# Simple_VGA.net
KiCad netlist of a schematic drawn in EAGLE
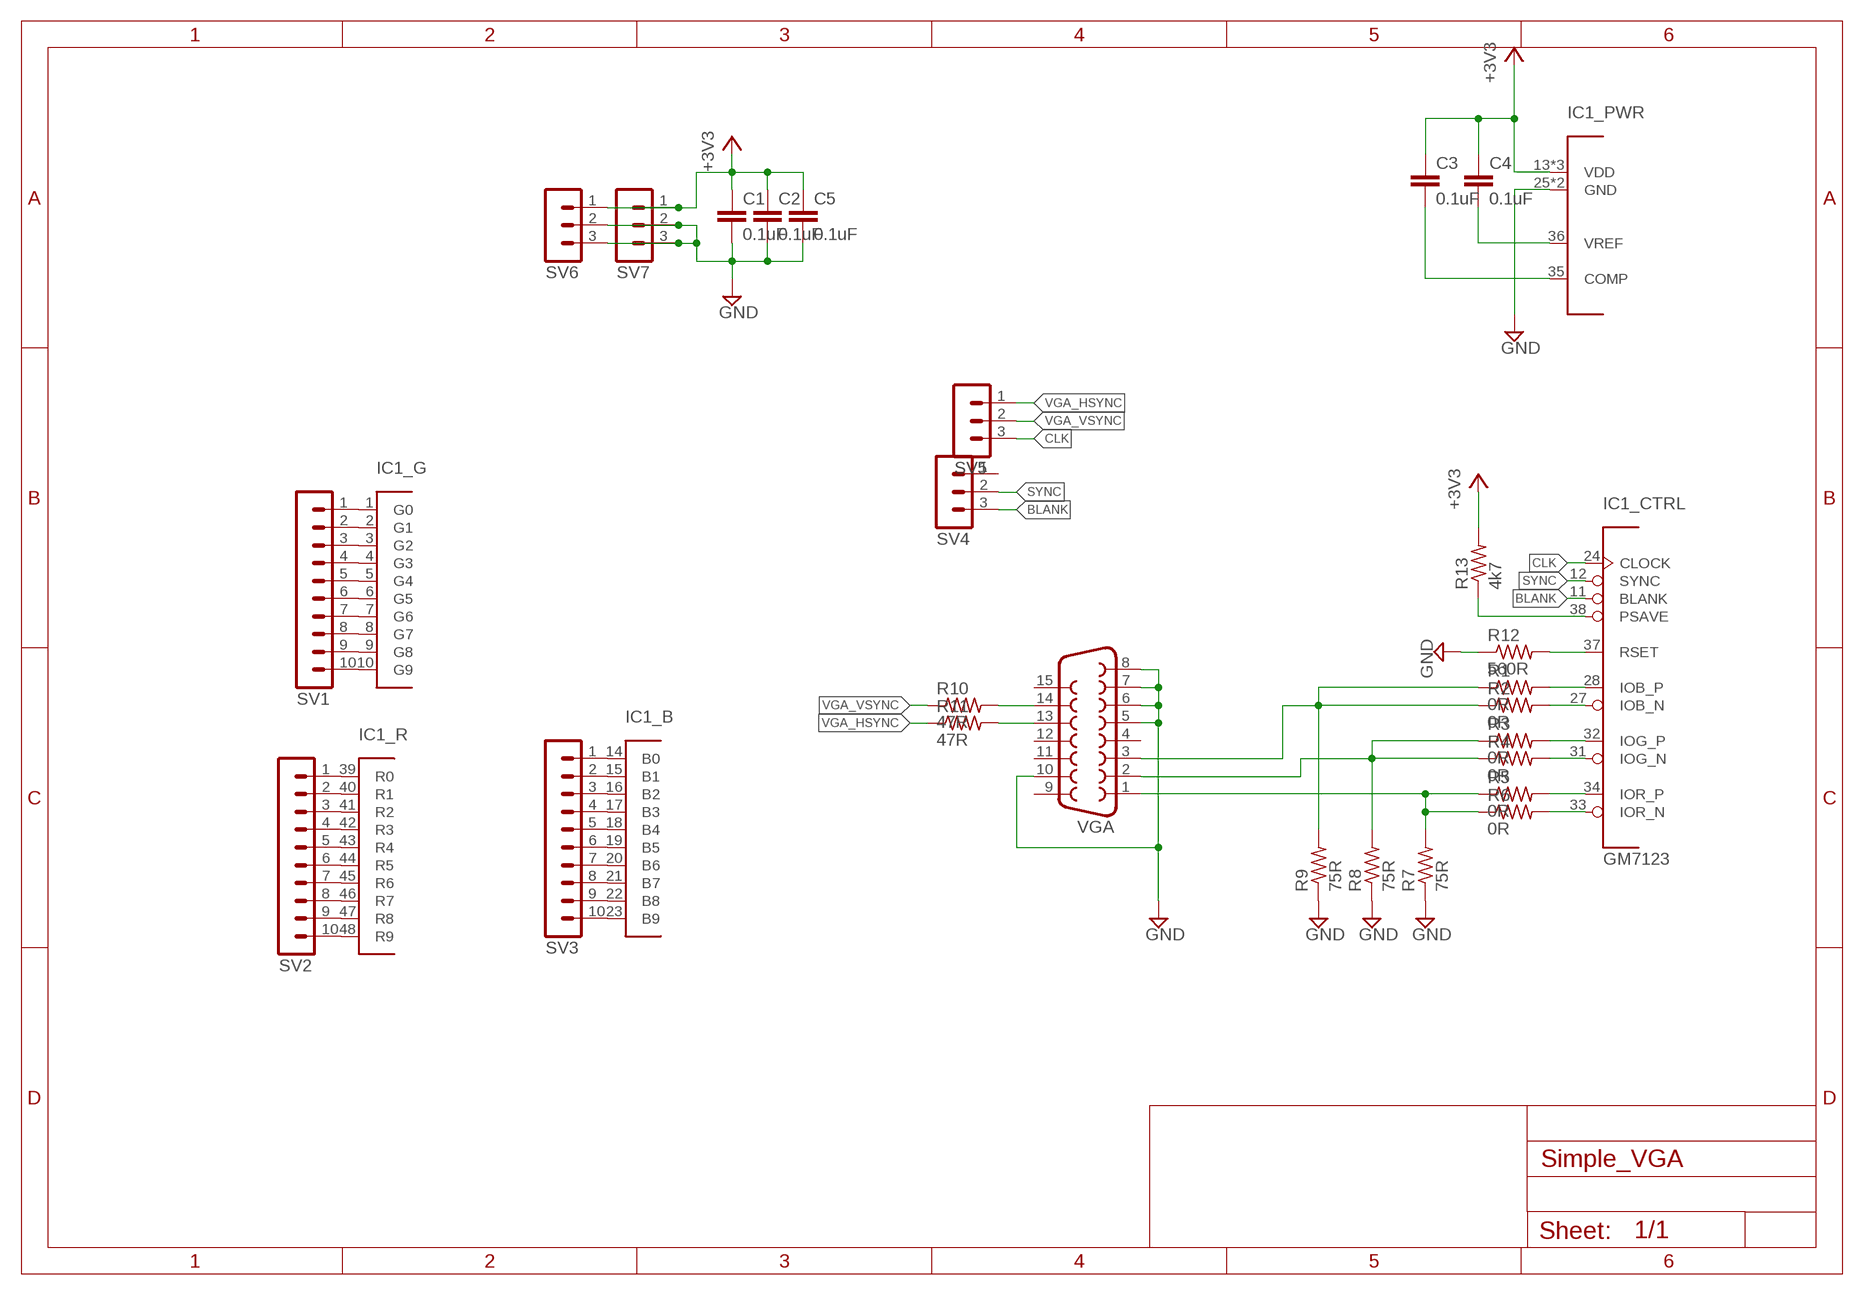
[diagram p0: schematic, sheet 1]

(export (version "E")
  (design (tool "Eeschema 10.0.6"))
  (components
    (comp (ref "C1")
      (value "0.1uF")
      (footprint "eagle-import:C1206")
      (libsource (lib "eagle-import") (part "C-EUC1206"))
    )
    (comp (ref "C2")
      (value "0.1uF")
      (footprint "eagle-import:C1206")
      (libsource (lib "eagle-import") (part "C-EUC1206"))
    )
    (comp (ref "C3")
      (value "0.1uF")
      (footprint "eagle-import:C1206")
      (libsource (lib "eagle-import") (part "C-EUC1206"))
    )
    (comp (ref "C4")
      (value "0.1uF")
      (footprint "eagle-import:C1206")
      (libsource (lib "eagle-import") (part "C-EUC1206"))
    )
    (comp (ref "C5")
      (value "0.1uF")
      (footprint "eagle-import:C1206")
      (libsource (lib "eagle-import") (part "C-EUC1206"))
    )
    (comp (ref "IC1")
      (value "GM7123")
      (footprint "eagle-import:TQFP48")
      (libsource (lib "eagle-import") (part "GM7123"))
    )
    (comp (ref "R1")
      (value "0R")
      (footprint "eagle-import:R1206")
      (libsource (lib "eagle-import") (part "R-US_R1206"))
    )
    (comp (ref "R2")
      (value "0R")
      (footprint "eagle-import:R1206")
      (libsource (lib "eagle-import") (part "R-US_R1206"))
    )
    (comp (ref "R3")
      (value "0R")
      (footprint "eagle-import:R1206")
      (libsource (lib "eagle-import") (part "R-US_R1206"))
    )
    (comp (ref "R4")
      (value "0R")
      (footprint "eagle-import:R1206")
      (libsource (lib "eagle-import") (part "R-US_R1206"))
    )
    (comp (ref "R5")
      (value "0R")
      (footprint "eagle-import:R1206")
      (libsource (lib "eagle-import") (part "R-US_R1206"))
    )
    (comp (ref "R6")
      (value "0R")
      (footprint "eagle-import:R1206")
      (libsource (lib "eagle-import") (part "R-US_R1206"))
    )
    (comp (ref "R7")
      (value "75R")
      (footprint "eagle-import:R1206")
      (libsource (lib "eagle-import") (part "R-US_R1206"))
    )
    (comp (ref "R8")
      (value "75R")
      (footprint "eagle-import:R1206")
      (libsource (lib "eagle-import") (part "R-US_R1206"))
    )
    (comp (ref "R9")
      (value "75R")
      (footprint "eagle-import:R1206")
      (libsource (lib "eagle-import") (part "R-US_R1206"))
    )
    (comp (ref "R10")
      (value "47R")
      (footprint "eagle-import:R1206")
      (libsource (lib "eagle-import") (part "R-US_R1206"))
    )
    (comp (ref "R11")
      (value "47R")
      (footprint "eagle-import:R1206")
      (libsource (lib "eagle-import") (part "R-US_R1206"))
    )
    (comp (ref "R12")
      (value "560R")
      (footprint "eagle-import:R1206")
      (libsource (lib "eagle-import") (part "R-US_R1206"))
    )
    (comp (ref "R13")
      (value "4k7")
      (footprint "eagle-import:R1206")
      (libsource (lib "eagle-import") (part "R-US_R1206"))
    )
    (comp (ref "SV1")
      (value "MA10-1")
      (footprint "eagle-import:MA10-1")
      (libsource (lib "eagle-import") (part "MA10-1"))
    )
    (comp (ref "SV2")
      (value "MA10-1")
      (footprint "eagle-import:MA10-1")
      (fields (field (name "OC_FARNELL") "unknown") (field (name "OC_NEWARK") "unknown"))
      (libsource (lib "eagle-import") (part "MA10-1"))
    )
    (comp (ref "SV3")
      (value "MA10-1")
      (footprint "eagle-import:MA10-1")
      (fields (field (name "OC_FARNELL") "unknown") (field (name "OC_NEWARK") "unknown"))
      (libsource (lib "eagle-import") (part "MA10-1"))
    )
    (comp (ref "SV4")
      (value "MA03-1")
      (footprint "eagle-import:MA03-1")
      (fields (field (name "OC_FARNELL") "unknown") (field (name "OC_NEWARK") "unknown"))
      (libsource (lib "eagle-import") (part "MA03-1"))
    )
    (comp (ref "SV5")
      (value "MA03-1")
      (footprint "eagle-import:MA03-1")
      (libsource (lib "eagle-import") (part "MA03-1"))
    )
    (comp (ref "SV6")
      (value "MA03-1")
      (footprint "eagle-import:MA03-1")
      (fields (field (name "OC_FARNELL") "unknown") (field (name "OC_NEWARK") "unknown"))
      (libsource (lib "eagle-import") (part "MA03-1"))
    )
    (comp (ref "SV7")
      (value "MA03-1")
      (footprint "eagle-import:MA03-1")
      (fields (field (name "OC_FARNELL") "unknown") (field (name "OC_NEWARK") "unknown"))
      (libsource (lib "eagle-import") (part "MA03-1"))
    )
    (comp (ref "VGA")
      (value "F15HDH")
      (footprint "eagle-import:HDF15H")
      (libsource (lib "eagle-import") (part "F15HDH"))
    )
  )
  (nets
    (net (code "1") (name "+3V3") (class "Default")
      (node (ref "C1") (pin "1") (pinfunction "1_1") (pintype "passive"))
      (node (ref "C2") (pin "1") (pinfunction "1_1") (pintype "passive"))
      (node (ref "C3") (pin "1") (pinfunction "1_1") (pintype "passive"))
      (node (ref "C4") (pin "1") (pinfunction "1_1") (pintype "passive"))
      (node (ref "C5") (pin "1") (pinfunction "1_1") (pintype "passive"))
      (node (ref "IC1") (pin "13") (pinfunction "VDD_13") (pintype "power_in"))
      (node (ref "IC1") (pin "29") (pinfunction "VDD_29") (pintype "power_in"))
      (node (ref "IC1") (pin "30") (pinfunction "VDD_30") (pintype "power_in"))
      (node (ref "R13") (pin "2") (pinfunction "2_2") (pintype "passive"))
      (node (ref "SV6") (pin "1") (pinfunction "1_1") (pintype "passive"))
      (node (ref "SV7") (pin "1") (pinfunction "1_1") (pintype "passive"))
    )
    (net (code "2") (name "BLANK") (class "Default")
      (node (ref "IC1") (pin "11") (pinfunction "BLANK_11") (pintype "input"))
      (node (ref "SV4") (pin "3") (pinfunction "3_3") (pintype "passive"))
    )
    (net (code "3") (name "CLK") (class "Default")
      (node (ref "IC1") (pin "24") (pinfunction "CLOCK_24") (pintype "input"))
      (node (ref "SV5") (pin "3") (pinfunction "3_3") (pintype "passive"))
    )
    (net (code "4") (name "GND") (class "Default")
      (node (ref "C1") (pin "2") (pinfunction "2_2") (pintype "passive"))
      (node (ref "C2") (pin "2") (pinfunction "2_2") (pintype "passive"))
      (node (ref "C5") (pin "2") (pinfunction "2_2") (pintype "passive"))
      (node (ref "IC1") (pin "25") (pinfunction "GND_25") (pintype "power_in"))
      (node (ref "IC1") (pin "26") (pinfunction "GND_26") (pintype "power_in"))
      (node (ref "R12") (pin "1") (pinfunction "1_1") (pintype "passive"))
      (node (ref "R7") (pin "1") (pinfunction "1_1") (pintype "passive"))
      (node (ref "R8") (pin "1") (pinfunction "1_1") (pintype "passive"))
      (node (ref "R9") (pin "1") (pinfunction "1_1") (pintype "passive"))
      (node (ref "SV6") (pin "2") (pinfunction "2_2") (pintype "passive"))
      (node (ref "SV6") (pin "3") (pinfunction "3_3") (pintype "passive"))
      (node (ref "SV7") (pin "2") (pinfunction "2_2") (pintype "passive"))
      (node (ref "SV7") (pin "3") (pinfunction "3_3") (pintype "passive"))
      (node (ref "VGA") (pin "10") (pinfunction "10_10") (pintype "passive"))
      (node (ref "VGA") (pin "5") (pinfunction "5_5") (pintype "passive"))
      (node (ref "VGA") (pin "6") (pinfunction "6_6") (pintype "passive"))
      (node (ref "VGA") (pin "7") (pinfunction "7_7") (pintype "passive"))
      (node (ref "VGA") (pin "8") (pinfunction "8_8") (pintype "passive"))
    )
    (net (code "5") (name "Net-(IC1A-B0)") (class "Default")
      (node (ref "IC1") (pin "14") (pinfunction "B0_14") (pintype "input"))
      (node (ref "SV3") (pin "1") (pinfunction "1_1") (pintype "passive"))
    )
    (net (code "6") (name "Net-(IC1A-B1)") (class "Default")
      (node (ref "IC1") (pin "15") (pinfunction "B1_15") (pintype "input"))
      (node (ref "SV3") (pin "2") (pinfunction "2_2") (pintype "passive"))
    )
    (net (code "7") (name "Net-(IC1A-B2)") (class "Default")
      (node (ref "IC1") (pin "16") (pinfunction "B2_16") (pintype "input"))
      (node (ref "SV3") (pin "3") (pinfunction "3_3") (pintype "passive"))
    )
    (net (code "8") (name "Net-(IC1A-B3)") (class "Default")
      (node (ref "IC1") (pin "17") (pinfunction "B3_17") (pintype "input"))
      (node (ref "SV3") (pin "4") (pinfunction "4_4") (pintype "passive"))
    )
    (net (code "9") (name "Net-(IC1A-B4)") (class "Default")
      (node (ref "IC1") (pin "18") (pinfunction "B4_18") (pintype "input"))
      (node (ref "SV3") (pin "5") (pinfunction "5_5") (pintype "passive"))
    )
    (net (code "10") (name "Net-(IC1A-B5)") (class "Default")
      (node (ref "IC1") (pin "19") (pinfunction "B5_19") (pintype "input"))
      (node (ref "SV3") (pin "6") (pinfunction "6_6") (pintype "passive"))
    )
    (net (code "11") (name "Net-(IC1A-B6)") (class "Default")
      (node (ref "IC1") (pin "20") (pinfunction "B6_20") (pintype "input"))
      (node (ref "SV3") (pin "7") (pinfunction "7_7") (pintype "passive"))
    )
    (net (code "12") (name "Net-(IC1A-B7)") (class "Default")
      (node (ref "IC1") (pin "21") (pinfunction "B7_21") (pintype "input"))
      (node (ref "SV3") (pin "8") (pinfunction "8_8") (pintype "passive"))
    )
    (net (code "13") (name "Net-(IC1A-B8)") (class "Default")
      (node (ref "IC1") (pin "22") (pinfunction "B8_22") (pintype "input"))
      (node (ref "SV3") (pin "9") (pinfunction "9_9") (pintype "passive"))
    )
    (net (code "14") (name "Net-(IC1A-B9)") (class "Default")
      (node (ref "IC1") (pin "23") (pinfunction "B9_23") (pintype "input"))
      (node (ref "SV3") (pin "10") (pinfunction "10_10") (pintype "passive"))
    )
    (net (code "15") (name "Net-(IC1B-IOB_N)") (class "Default")
      (node (ref "IC1") (pin "27") (pinfunction "IOB_N_27") (pintype "output"))
      (node (ref "R2") (pin "2") (pinfunction "2_2") (pintype "passive"))
    )
    (net (code "16") (name "Net-(IC1B-IOB_P)") (class "Default")
      (node (ref "IC1") (pin "28") (pinfunction "IOB_P_28") (pintype "output"))
      (node (ref "R1") (pin "2") (pinfunction "2_2") (pintype "passive"))
    )
    (net (code "17") (name "Net-(IC1B-IOG_N)") (class "Default")
      (node (ref "IC1") (pin "31") (pinfunction "IOG_N_31") (pintype "output"))
      (node (ref "R4") (pin "2") (pinfunction "2_2") (pintype "passive"))
    )
    (net (code "18") (name "Net-(IC1B-IOG_P)") (class "Default")
      (node (ref "IC1") (pin "32") (pinfunction "IOG_P_32") (pintype "output"))
      (node (ref "R3") (pin "2") (pinfunction "2_2") (pintype "passive"))
    )
    (net (code "19") (name "Net-(IC1B-IOR_N)") (class "Default")
      (node (ref "IC1") (pin "33") (pinfunction "IOR_N_33") (pintype "output"))
      (node (ref "R6") (pin "2") (pinfunction "2_2") (pintype "passive"))
    )
    (net (code "20") (name "Net-(IC1B-IOR_P)") (class "Default")
      (node (ref "IC1") (pin "34") (pinfunction "IOR_P_34") (pintype "output"))
      (node (ref "R5") (pin "2") (pinfunction "2_2") (pintype "passive"))
    )
    (net (code "21") (name "Net-(IC1B-PSAVE)") (class "Default")
      (node (ref "IC1") (pin "38") (pinfunction "PSAVE_38") (pintype "input"))
      (node (ref "R13") (pin "1") (pinfunction "1_1") (pintype "passive"))
    )
    (net (code "22") (name "Net-(IC1B-RSET)") (class "Default")
      (node (ref "IC1") (pin "37") (pinfunction "RSET_37") (pintype "input"))
      (node (ref "R12") (pin "2") (pinfunction "2_2") (pintype "passive"))
    )
    (net (code "23") (name "Net-(IC1C-G0)") (class "Default")
      (node (ref "IC1") (pin "1") (pinfunction "G0_1") (pintype "input"))
      (node (ref "SV1") (pin "1") (pinfunction "1_1") (pintype "passive"))
    )
    (net (code "24") (name "Net-(IC1C-G1)") (class "Default")
      (node (ref "IC1") (pin "2") (pinfunction "G1_2") (pintype "input"))
      (node (ref "SV1") (pin "2") (pinfunction "2_2") (pintype "passive"))
    )
    (net (code "25") (name "Net-(IC1C-G2)") (class "Default")
      (node (ref "IC1") (pin "3") (pinfunction "G2_3") (pintype "input"))
      (node (ref "SV1") (pin "3") (pinfunction "3_3") (pintype "passive"))
    )
    (net (code "26") (name "Net-(IC1C-G3)") (class "Default")
      (node (ref "IC1") (pin "4") (pinfunction "G3_4") (pintype "input"))
      (node (ref "SV1") (pin "4") (pinfunction "4_4") (pintype "passive"))
    )
    (net (code "27") (name "Net-(IC1C-G4)") (class "Default")
      (node (ref "IC1") (pin "5") (pinfunction "G4_5") (pintype "input"))
      (node (ref "SV1") (pin "5") (pinfunction "5_5") (pintype "passive"))
    )
    (net (code "28") (name "Net-(IC1C-G5)") (class "Default")
      (node (ref "IC1") (pin "6") (pinfunction "G5_6") (pintype "input"))
      (node (ref "SV1") (pin "6") (pinfunction "6_6") (pintype "passive"))
    )
    (net (code "29") (name "Net-(IC1C-G6)") (class "Default")
      (node (ref "IC1") (pin "7") (pinfunction "G6_7") (pintype "input"))
      (node (ref "SV1") (pin "7") (pinfunction "7_7") (pintype "passive"))
    )
    (net (code "30") (name "Net-(IC1C-G7)") (class "Default")
      (node (ref "IC1") (pin "8") (pinfunction "G7_8") (pintype "input"))
      (node (ref "SV1") (pin "8") (pinfunction "8_8") (pintype "passive"))
    )
    (net (code "31") (name "Net-(IC1C-G8)") (class "Default")
      (node (ref "IC1") (pin "9") (pinfunction "G8_9") (pintype "input"))
      (node (ref "SV1") (pin "9") (pinfunction "9_9") (pintype "passive"))
    )
    (net (code "32") (name "Net-(IC1C-G9)") (class "Default")
      (node (ref "IC1") (pin "10") (pinfunction "G9_10") (pintype "input"))
      (node (ref "SV1") (pin "10") (pinfunction "10_10") (pintype "passive"))
    )
    (net (code "33") (name "Net-(IC1D-COMP)") (class "Default")
      (node (ref "C3") (pin "2") (pinfunction "2_2") (pintype "passive"))
      (node (ref "IC1") (pin "35") (pinfunction "COMP_35") (pintype "power_in"))
    )
    (net (code "34") (name "Net-(IC1D-VREF)") (class "Default")
      (node (ref "C4") (pin "2") (pinfunction "2_2") (pintype "passive"))
      (node (ref "IC1") (pin "36") (pinfunction "VREF_36") (pintype "power_in"))
    )
    (net (code "35") (name "Net-(IC1E-R0)") (class "Default")
      (node (ref "IC1") (pin "39") (pinfunction "R0_39") (pintype "input"))
      (node (ref "SV2") (pin "1") (pinfunction "1_1") (pintype "passive"))
    )
    (net (code "36") (name "Net-(IC1E-R1)") (class "Default")
      (node (ref "IC1") (pin "40") (pinfunction "R1_40") (pintype "input"))
      (node (ref "SV2") (pin "2") (pinfunction "2_2") (pintype "passive"))
    )
    (net (code "37") (name "Net-(IC1E-R2)") (class "Default")
      (node (ref "IC1") (pin "41") (pinfunction "R2_41") (pintype "input"))
      (node (ref "SV2") (pin "3") (pinfunction "3_3") (pintype "passive"))
    )
    (net (code "38") (name "Net-(IC1E-R3)") (class "Default")
      (node (ref "IC1") (pin "42") (pinfunction "R3_42") (pintype "input"))
      (node (ref "SV2") (pin "4") (pinfunction "4_4") (pintype "passive"))
    )
    (net (code "39") (name "Net-(IC1E-R4)") (class "Default")
      (node (ref "IC1") (pin "43") (pinfunction "R4_43") (pintype "input"))
      (node (ref "SV2") (pin "5") (pinfunction "5_5") (pintype "passive"))
    )
    (net (code "40") (name "Net-(IC1E-R5)") (class "Default")
      (node (ref "IC1") (pin "44") (pinfunction "R5_44") (pintype "input"))
      (node (ref "SV2") (pin "6") (pinfunction "6_6") (pintype "passive"))
    )
    (net (code "41") (name "Net-(IC1E-R6)") (class "Default")
      (node (ref "IC1") (pin "45") (pinfunction "R6_45") (pintype "input"))
      (node (ref "SV2") (pin "7") (pinfunction "7_7") (pintype "passive"))
    )
    (net (code "42") (name "Net-(IC1E-R7)") (class "Default")
      (node (ref "IC1") (pin "46") (pinfunction "R7_46") (pintype "input"))
      (node (ref "SV2") (pin "8") (pinfunction "8_8") (pintype "passive"))
    )
    (net (code "43") (name "Net-(IC1E-R8)") (class "Default")
      (node (ref "IC1") (pin "47") (pinfunction "R8_47") (pintype "input"))
      (node (ref "SV2") (pin "9") (pinfunction "9_9") (pintype "passive"))
    )
    (net (code "44") (name "Net-(IC1E-R9)") (class "Default")
      (node (ref "IC1") (pin "48") (pinfunction "R9_48") (pintype "input"))
      (node (ref "SV2") (pin "10") (pinfunction "10_10") (pintype "passive"))
    )
    (net (code "45") (name "Net-(R1-Pad1)") (class "Default")
      (node (ref "R1") (pin "1") (pinfunction "1_1") (pintype "passive"))
      (node (ref "R2") (pin "1") (pinfunction "1_1") (pintype "passive"))
      (node (ref "R9") (pin "2") (pinfunction "2_2") (pintype "passive"))
      (node (ref "VGA") (pin "3") (pinfunction "3_3") (pintype "passive"))
    )
    (net (code "46") (name "Net-(R3-Pad1)") (class "Default")
      (node (ref "R3") (pin "1") (pinfunction "1_1") (pintype "passive"))
      (node (ref "R4") (pin "1") (pinfunction "1_1") (pintype "passive"))
      (node (ref "R8") (pin "2") (pinfunction "2_2") (pintype "passive"))
      (node (ref "VGA") (pin "2") (pinfunction "2_2") (pintype "passive"))
    )
    (net (code "47") (name "Net-(R5-Pad1)") (class "Default")
      (node (ref "R5") (pin "1") (pinfunction "1_1") (pintype "passive"))
      (node (ref "R6") (pin "1") (pinfunction "1_1") (pintype "passive"))
      (node (ref "R7") (pin "2") (pinfunction "2_2") (pintype "passive"))
      (node (ref "VGA") (pin "1") (pinfunction "1_1") (pintype "passive"))
    )
    (net (code "48") (name "Net-(R10-Pad2)") (class "Default")
      (node (ref "R10") (pin "2") (pinfunction "2_2") (pintype "passive"))
      (node (ref "VGA") (pin "14") (pinfunction "14_14") (pintype "passive"))
    )
    (net (code "49") (name "Net-(R11-Pad2)") (class "Default")
      (node (ref "R11") (pin "2") (pinfunction "2_2") (pintype "passive"))
      (node (ref "VGA") (pin "13") (pinfunction "13_13") (pintype "passive"))
    )
    (net (code "50") (name "SYNC") (class "Default")
      (node (ref "IC1") (pin "12") (pinfunction "SYNC_12") (pintype "input"))
      (node (ref "SV4") (pin "2") (pinfunction "2_2") (pintype "passive"))
    )
    (net (code "51") (name "VGA_HSYNC") (class "Default")
      (node (ref "R11") (pin "1") (pinfunction "1_1") (pintype "passive"))
      (node (ref "SV5") (pin "1") (pinfunction "1_1") (pintype "passive"))
    )
    (net (code "52") (name "VGA_VSYNC") (class "Default")
      (node (ref "R10") (pin "1") (pinfunction "1_1") (pintype "passive"))
      (node (ref "SV5") (pin "2") (pinfunction "2_2") (pintype "passive"))
    )
    (net (code "53") (name "unconnected-(SV4-Pad1)") (class "Default")
      (node (ref "SV4") (pin "1") (pinfunction "1_1") (pintype "passive"))
    )
    (net (code "54") (name "unconnected-(VGA-Pad4)") (class "Default")
      (node (ref "VGA") (pin "4") (pinfunction "4_4") (pintype "passive"))
    )
    (net (code "55") (name "unconnected-(VGA-Pad9)") (class "Default")
      (node (ref "VGA") (pin "9") (pinfunction "9_9") (pintype "passive"))
    )
    (net (code "56") (name "unconnected-(VGA-Pad11)") (class "Default")
      (node (ref "VGA") (pin "11") (pinfunction "11_11") (pintype "passive"))
    )
    (net (code "57") (name "unconnected-(VGA-Pad12)") (class "Default")
      (node (ref "VGA") (pin "12") (pinfunction "12_12") (pintype "passive"))
    )
    (net (code "58") (name "unconnected-(VGA-Pad15)") (class "Default")
      (node (ref "VGA") (pin "15") (pinfunction "15_15") (pintype "passive"))
    )
  )
)
